# gasp_semg_bandpass_2nd_order.net
KiCad netlist of a schematic drawn in Altium Designer
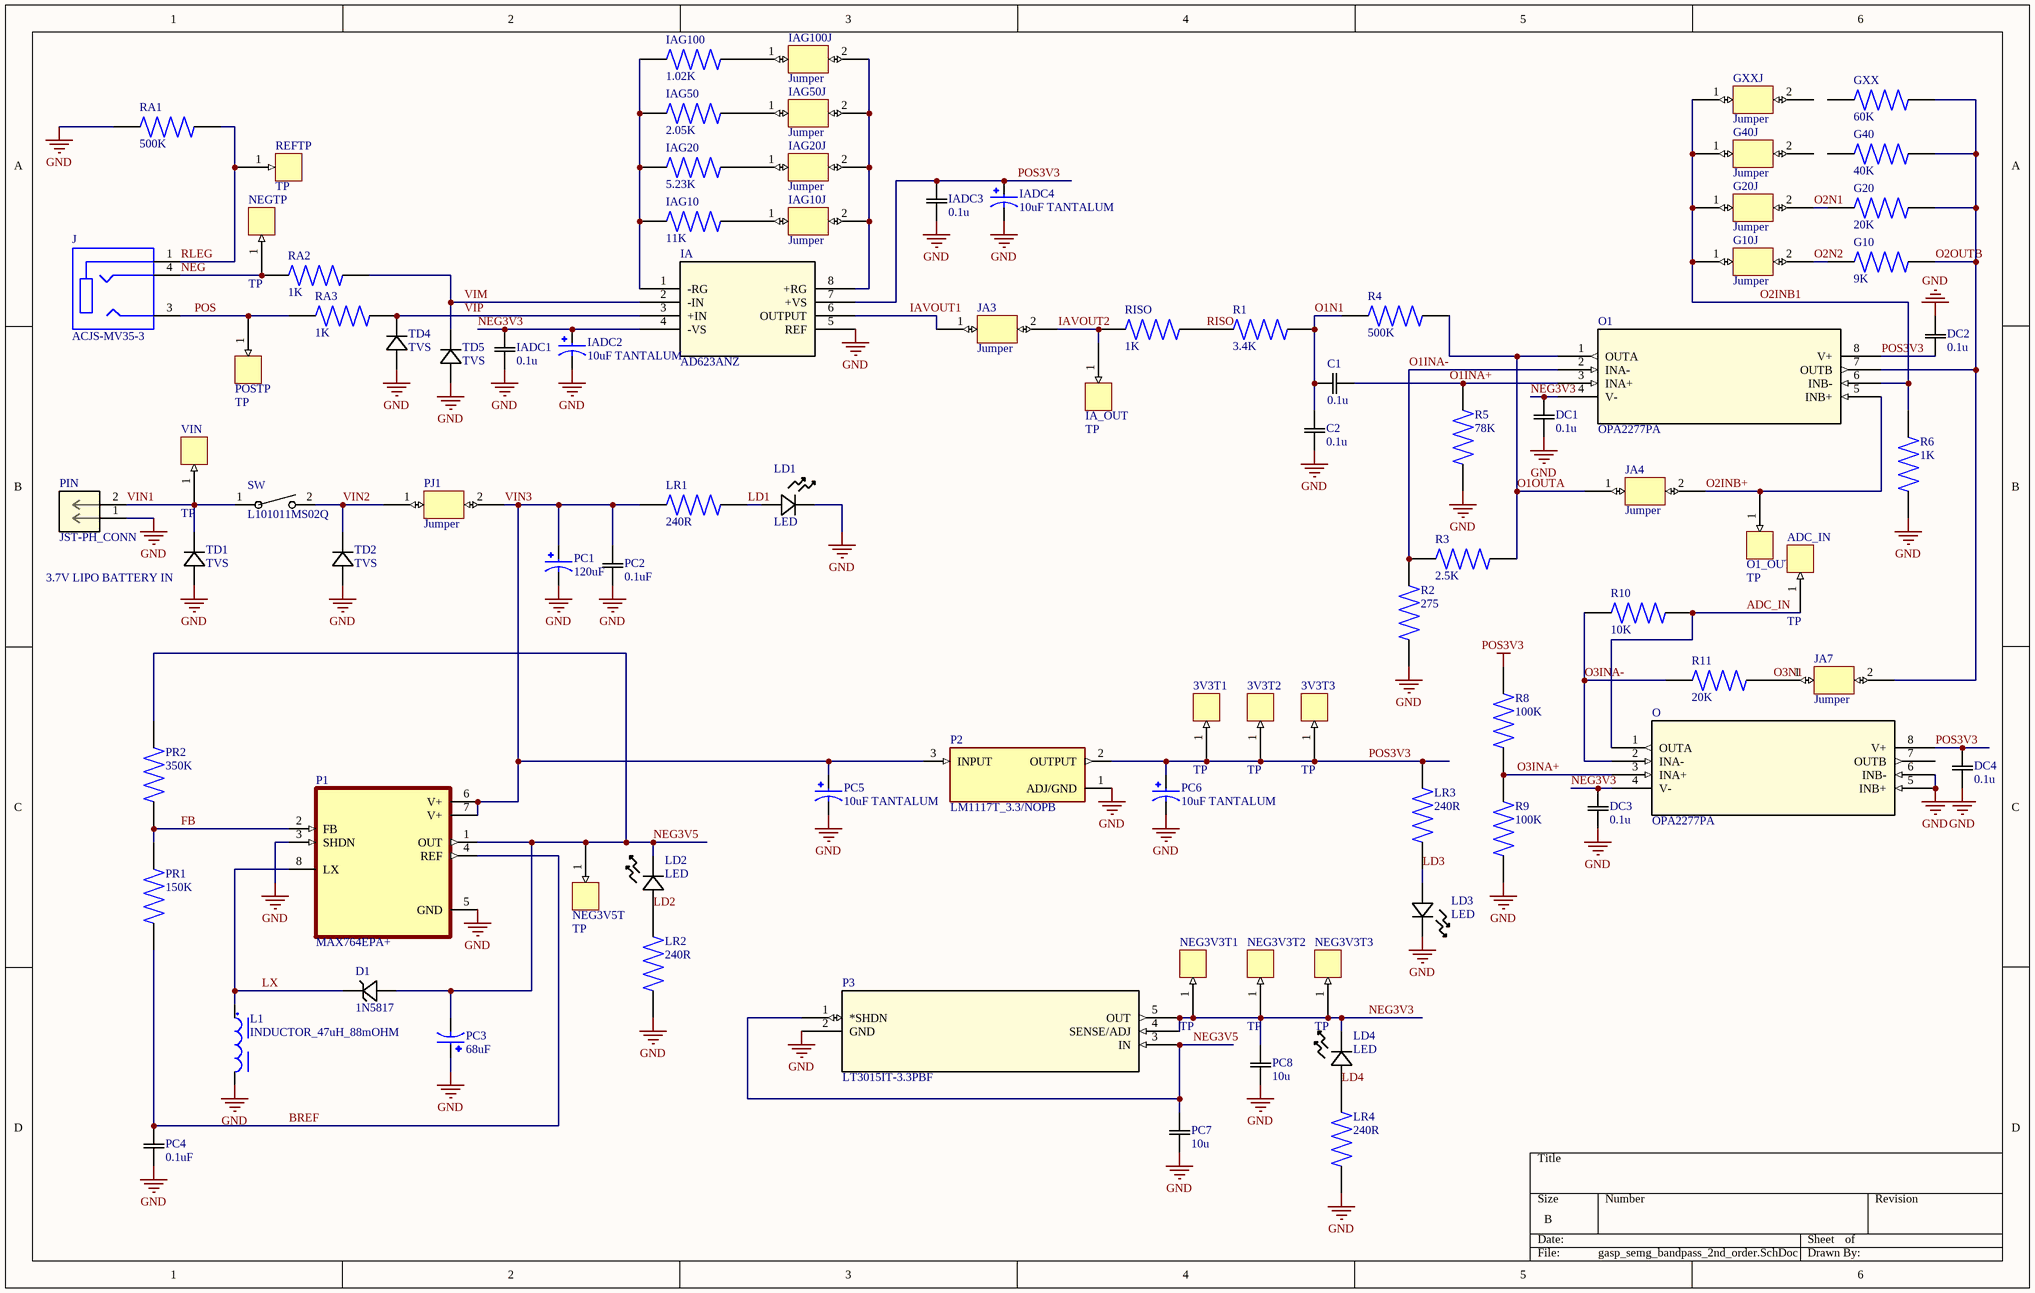
[diagram p0: gasp_semg_bandpass_2nd_order.SchDoc]

(export (version "E")
  (design (tool "Eeschema 10.0.6"))
  (components
    (comp (ref "3V3T1") (value "TP") (footprint "Test Point2") (libsource (lib "") (part "TP_1")))
    (comp (ref "3V3T2") (value "TP") (footprint "Test Point2") (libsource (lib "") (part "TP_1")))
    (comp (ref "3V3T3") (value "TP") (footprint "Test Point2") (libsource (lib "") (part "TP_1")))
    (comp (ref "ADC_IN") (value "TP") (footprint "Test Point2") (libsource (lib "") (part "TP_1")))
    (comp (ref "C1")
      (value "0.1u")
      (footprint "Axial")
      (description "Capacitor axial through-hole.")
      (fields
        (field (name "MANUFACTURER_PART_NUMBER") "C410C821J3G5TA")
        (field (name "COPYRIGHT") "Copyright (C) 2025 Ultra Librarian. All rights reserved.")
      )
      (libsource (lib "CAPACITOR_AXIAL_THROUGH_HOLE") (part "Cap"))
    )
    (comp (ref "C2")
      (value "0.1u")
      (footprint "Axial")
      (description "Capacitor axial through-hole.")
      (fields
        (field (name "MANUFACTURER_PART_NUMBER") "C410C821J3G5TA")
        (field (name "COPYRIGHT") "Copyright (C) 2025 Ultra Librarian. All rights reserved.")
      )
      (libsource (lib "CAPACITOR_AXIAL_THROUGH_HOLE") (part "Cap"))
    )
    (comp (ref "D1")
      (value "1N5817")
      (footprint "DO-41_STM")
      (description "20 V, 1 A axial Power Schottky Rectifier")
      (fields (field (name "COPYRIGHT") "Copyright (C) 2025 Ultra Librarian. All rights reserved."))
      (libsource (lib "DIODE_SCHOTTKY_1N5817") (part "1N5817"))
    )
    (comp (ref "DC1")
      (value "0.1u")
      (footprint "Axial")
      (description "Capacitor axial through-hole.")
      (fields
        (field (name "MANUFACTURER_PART_NUMBER") "C410C821J3G5TA")
        (field (name "COPYRIGHT") "Copyright (C) 2025 Ultra Librarian. All rights reserved.")
      )
      (libsource (lib "CAPACITOR_AXIAL_THROUGH_HOLE") (part "Cap"))
    )
    (comp (ref "DC2")
      (value "0.1u")
      (footprint "Axial")
      (description "Capacitor axial through-hole.")
      (fields
        (field (name "MANUFACTURER_PART_NUMBER") "C410C821J3G5TA")
        (field (name "COPYRIGHT") "Copyright (C) 2025 Ultra Librarian. All rights reserved.")
      )
      (libsource (lib "CAPACITOR_AXIAL_THROUGH_HOLE") (part "Cap"))
    )
    (comp (ref "DC3")
      (value "0.1u")
      (footprint "Axial")
      (description "Capacitor axial through-hole.")
      (fields
        (field (name "MANUFACTURER_PART_NUMBER") "C410C821J3G5TA")
        (field (name "COPYRIGHT") "Copyright (C) 2025 Ultra Librarian. All rights reserved.")
      )
      (libsource (lib "CAPACITOR_AXIAL_THROUGH_HOLE") (part "Cap"))
    )
    (comp (ref "DC4")
      (value "0.1u")
      (footprint "Axial")
      (description "Capacitor axial through-hole.")
      (fields
        (field (name "MANUFACTURER_PART_NUMBER") "C410C821J3G5TA")
        (field (name "COPYRIGHT") "Copyright (C) 2025 Ultra Librarian. All rights reserved.")
      )
      (libsource (lib "CAPACITOR_AXIAL_THROUGH_HOLE") (part "Cap"))
    )
    (comp (ref "G10")
      (value "9K")
      (footprint "Axial")
      (description "Through-hole resistor axial.")
      (fields (field (name "MF") "Yageo") (field (name "MP") "MFR-25FBF52-10K"))
      (libsource (lib "RESISTOR_THROUGH_HOLE") (part "Resistor"))
    )
    (comp (ref "G10J")
      (value "Jumper")
      (footprint "2-Pin Jumper")
      (description "0.1\" 2 pin jumper")
      (libsource (lib "JUMPER") (part "Jumper"))
    )
    (comp (ref "G20")
      (value "20K")
      (footprint "Axial")
      (description "Through-hole resistor axial.")
      (fields (field (name "MF") "Yageo") (field (name "MP") "MFR-25FBF52-10K"))
      (libsource (lib "RESISTOR_THROUGH_HOLE") (part "Resistor"))
    )
    (comp (ref "G20J")
      (value "Jumper")
      (footprint "2-Pin Jumper")
      (description "0.1\" 2 pin jumper")
      (libsource (lib "JUMPER") (part "Jumper"))
    )
    (comp (ref "G40")
      (value "40K")
      (footprint "Axial")
      (description "Through-hole resistor axial.")
      (fields (field (name "MF") "Yageo") (field (name "MP") "MFR-25FBF52-10K"))
      (libsource (lib "RESISTOR_THROUGH_HOLE") (part "Resistor"))
    )
    (comp (ref "G40J")
      (value "Jumper")
      (footprint "2-Pin Jumper")
      (description "0.1\" 2 pin jumper")
      (libsource (lib "JUMPER") (part "Jumper"))
    )
    (comp (ref "GXX")
      (value "60K")
      (footprint "Axial")
      (description "Through-hole resistor axial.")
      (fields (field (name "MF") "Yageo") (field (name "MP") "MFR-25FBF52-10K"))
      (libsource (lib "RESISTOR_THROUGH_HOLE") (part "Resistor"))
    )
    (comp (ref "GXXJ")
      (value "Jumper")
      (footprint "2-Pin Jumper")
      (description "0.1\" 2 pin jumper")
      (libsource (lib "JUMPER") (part "Jumper"))
    )
    (comp (ref "IA")
      (value "AD623ANZ")
      (footprint "8-PDIP")
      (description "Single and Dual-Supply, Rail-to-Rail, Low Cost Instrumentation Amplifier. AD623ANZ.")
      (fields (field (name "COPYRIGHT") "Copyright (C) 2025 Ultra Librarian. All rights reserved."))
      (libsource (lib "INSTRUMENTATION_AMP_DUAL_SINGLE_SUPPLY_AD623ANZ") (part "AD623ANZ"))
    )
    (comp (ref "IADC1")
      (value "0.1u")
      (footprint "Axial")
      (description "Capacitor axial through-hole.")
      (fields
        (field (name "MANUFACTURER_PART_NUMBER") "C410C821J3G5TA")
        (field (name "COPYRIGHT") "Copyright (C) 2025 Ultra Librarian. All rights reserved.")
      )
      (libsource (lib "CAPACITOR_AXIAL_THROUGH_HOLE") (part "Cap"))
    )
    (comp (ref "IADC2")
      (value "10uF TANTALUM")
      (footprint "CAP RADIAL")
      (description "CAPACITOR RADIAL.")
      (fields (field (name "MF") "Panasonic") (field (name "MP") "ECA1HM101"))
      (libsource (lib "") (part "CAP_1"))
    )
    (comp (ref "IADC3")
      (value "0.1u")
      (footprint "Axial")
      (description "Capacitor axial through-hole.")
      (fields
        (field (name "MANUFACTURER_PART_NUMBER") "C410C821J3G5TA")
        (field (name "COPYRIGHT") "Copyright (C) 2025 Ultra Librarian. All rights reserved.")
      )
      (libsource (lib "CAPACITOR_AXIAL_THROUGH_HOLE") (part "Cap"))
    )
    (comp (ref "IADC4")
      (value "10uF TANTALUM")
      (footprint "CAP RADIAL")
      (description "CAPACITOR RADIAL.")
      (fields (field (name "MF") "Panasonic") (field (name "MP") "ECA1HM101"))
      (libsource (lib "") (part "CAP_1"))
    )
    (comp (ref "IAG10")
      (value "11K")
      (footprint "Axial")
      (description "Through-hole resistor axial.")
      (fields (field (name "MF") "Yageo") (field (name "MP") "MFR-25FBF52-10K"))
      (libsource (lib "RESISTOR_THROUGH_HOLE") (part "Resistor"))
    )
    (comp (ref "IAG10J")
      (value "Jumper")
      (footprint "2-Pin Jumper")
      (description "0.1\" 2 pin jumper")
      (libsource (lib "JUMPER") (part "Jumper"))
    )
    (comp (ref "IAG20")
      (value "5.23K")
      (footprint "Axial")
      (description "Through-hole resistor axial.")
      (fields (field (name "MF") "Yageo") (field (name "MP") "MFR-25FBF52-10K"))
      (libsource (lib "RESISTOR_THROUGH_HOLE") (part "Resistor"))
    )
    (comp (ref "IAG20J")
      (value "Jumper")
      (footprint "2-Pin Jumper")
      (description "0.1\" 2 pin jumper")
      (libsource (lib "JUMPER") (part "Jumper"))
    )
    (comp (ref "IAG50")
      (value "2.05K")
      (footprint "Axial")
      (description "Through-hole resistor axial.")
      (fields (field (name "MF") "Yageo") (field (name "MP") "MFR-25FBF52-10K"))
      (libsource (lib "RESISTOR_THROUGH_HOLE") (part "Resistor"))
    )
    (comp (ref "IAG50J")
      (value "Jumper")
      (footprint "2-Pin Jumper")
      (description "0.1\" 2 pin jumper")
      (libsource (lib "JUMPER") (part "Jumper"))
    )
    (comp (ref "IAG100")
      (value "1.02K")
      (footprint "Axial")
      (description "Through-hole resistor axial.")
      (fields (field (name "MF") "Yageo") (field (name "MP") "MFR-25FBF52-10K"))
      (libsource (lib "RESISTOR_THROUGH_HOLE") (part "Resistor"))
    )
    (comp (ref "IAG100J")
      (value "Jumper")
      (footprint "2-Pin Jumper")
      (description "0.1\" 2 pin jumper")
      (libsource (lib "JUMPER") (part "Jumper"))
    )
    (comp (ref "IA_OUT") (value "TP") (footprint "Test Point2") (libsource (lib "") (part "TP_2")))
    (comp (ref "J")
      (value "ACJS-MV35-3")
      (footprint "AUDIO JACK II")
      (fields (field (name "MP") "SJ1-3553NG"))
      (libsource (lib "Audio Jack") (part "ACJS-MV35-3"))
    )
    (comp (ref "JA3")
      (value "Jumper")
      (footprint "2-Pin Jumper")
      (description "0.1\" 2 pin jumper")
      (libsource (lib "JUMPER") (part "Jumper"))
    )
    (comp (ref "JA4")
      (value "Jumper")
      (footprint "2-Pin Jumper")
      (description "0.1\" 2 pin jumper")
      (libsource (lib "JUMPER") (part "Jumper"))
    )
    (comp (ref "JA7")
      (value "Jumper")
      (footprint "2-Pin Jumper")
      (description "0.1\" 2 pin jumper")
      (libsource (lib "JUMPER") (part "Jumper"))
    )
    (comp (ref "L1")
      (value "INDUCTOR_47uH_88mOHM")
      (footprint "INDUCTOR_47uH_88mOHM")
      (fields (field (name "MF") "{'manufacturer': u'Wurth Electronics'}") (field (name "MP") "7447471470"))
      (libsource (lib "INDUCTOR_47uH_88mOHM_7447471470") (part "INDUCTOR_47uH_88mOHM"))
    )
    (comp (ref "LD1")
      (value "LED")
      (footprint "LED_5MM_RADIAL")
      (description "LED_5MM_RADIAL")
      (fields
        (field (name "MANUFACTURER_PART_NUMBER") "C503B-BCN-CV0Z0461")
        (field (name "COPYRIGHT") "Copyright (C) 2025 Ultra Librarian. All rights reserved.")
      )
      (libsource (lib "LED_5MM_RADIAL") (part "LED"))
    )
    (comp (ref "LD2")
      (value "LED")
      (footprint "LED_5MM_RADIAL")
      (description "LED_5MM_RADIAL")
      (fields
        (field (name "MANUFACTURER_PART_NUMBER") "C503B-BCN-CV0Z0461")
        (field (name "COPYRIGHT") "Copyright (C) 2025 Ultra Librarian. All rights reserved.")
      )
      (libsource (lib "LED_5MM_RADIAL") (part "LED"))
    )
    (comp (ref "LD3")
      (value "LED")
      (footprint "LED_5MM_RADIAL")
      (description "LED_5MM_RADIAL")
      (fields
        (field (name "MANUFACTURER_PART_NUMBER") "C503B-BCN-CV0Z0461")
        (field (name "COPYRIGHT") "Copyright (C) 2025 Ultra Librarian. All rights reserved.")
      )
      (libsource (lib "LED_5MM_RADIAL") (part "LED"))
    )
    (comp (ref "LD4")
      (value "LED")
      (footprint "LED_5MM_RADIAL")
      (description "LED_5MM_RADIAL")
      (fields
        (field (name "MANUFACTURER_PART_NUMBER") "C503B-BCN-CV0Z0461")
        (field (name "COPYRIGHT") "Copyright (C) 2025 Ultra Librarian. All rights reserved.")
      )
      (libsource (lib "LED_5MM_RADIAL") (part "LED"))
    )
    (comp (ref "LR1")
      (value "240R")
      (footprint "Axial")
      (description "Through-hole resistor axial.")
      (fields (field (name "MF") "Yageo") (field (name "MP") "MFR-25FBF52-10K"))
      (libsource (lib "RESISTOR_THROUGH_HOLE") (part "Resistor"))
    )
    (comp (ref "LR2")
      (value "240R")
      (footprint "Axial")
      (description "Through-hole resistor axial.")
      (fields (field (name "MF") "Yageo") (field (name "MP") "MFR-25FBF52-10K"))
      (libsource (lib "RESISTOR_THROUGH_HOLE") (part "Resistor"))
    )
    (comp (ref "LR3")
      (value "240R")
      (footprint "Axial")
      (description "Through-hole resistor axial.")
      (fields (field (name "MF") "Yageo") (field (name "MP") "MFR-25FBF52-10K"))
      (libsource (lib "RESISTOR_THROUGH_HOLE") (part "Resistor"))
    )
    (comp (ref "LR4")
      (value "240R")
      (footprint "Axial")
      (description "Through-hole resistor axial.")
      (fields (field (name "MF") "Yageo") (field (name "MP") "MFR-25FBF52-10K"))
      (libsource (lib "RESISTOR_THROUGH_HOLE") (part "Resistor"))
    )
    (comp (ref "NEG3V3T1") (value "TP") (footprint "Test Point2") (libsource (lib "") (part "TP_1")))
    (comp (ref "NEG3V3T2") (value "TP") (footprint "Test Point2") (libsource (lib "") (part "TP_1")))
    (comp (ref "NEG3V3T3") (value "TP") (footprint "Test Point2") (libsource (lib "") (part "TP_1")))
    (comp (ref "NEG3V5T") (value "TP") (footprint "Test Point2") (libsource (lib "") (part "TP_2")))
    (comp (ref "NEGTP") (value "TP") (footprint "Test Point2") (libsource (lib "") (part "TP_1")))
    (comp (ref "O")
      (value "OPA2277PA")
      (footprint "8-PDIP")
      (description "10ÂµV, 0.1ÂµV/ËšC, High-Precision, Low-Power Operational Amplifier 8-PDIP")
      (fields (field (name "COPYRIGHT") "Copyright (C) 2025 Ultra Librarian. All rights reserved."))
      (libsource (lib "OPAMP_DUAL_SUPPLY_8-PDIP_OPA2277PA") (part "OPA2277PA"))
    )
    (comp (ref "O1")
      (value "OPA2277PA")
      (footprint "8-PDIP")
      (description "10ÂµV, 0.1ÂµV/ËšC, High-Precision, Low-Power Operational Amplifier 8-PDIP")
      (fields (field (name "COPYRIGHT") "Copyright (C) 2025 Ultra Librarian. All rights reserved."))
      (libsource (lib "OPAMP_DUAL_SUPPLY_8-PDIP_OPA2277PA") (part "OPA2277PA"))
    )
    (comp (ref "O1_OUT") (value "TP") (footprint "Test Point2") (libsource (lib "") (part "TP_2")))
    (comp (ref "P1")
      (value "MAX764EPA+")
      (footprint "8-PDIP")
      (description "IC REG BCK BST ADJ/-5V 8DIP")
      (fields (field (name "MF") "Maxim Integrated"))
      (libsource (lib "BUCK_BOOST_-1V_TO_-16V_OUTPUT_MAX764EPA") (part "MAX764EPA+"))
    )
    (comp (ref "P2")
      (value "LM1117T_3.3/NOPB")
      (footprint "TO-220-3")
      (description "3.3V Linear Voltage Regulator IC Positive Fixed 1 Output 800mA TO-220-3.")
      (fields (field (name "MF") "Texas Instruments") (field (name "MP") "LM1117T-3.3/NOPB"))
      (libsource (lib "LDO_3V3_TO-220-3_LM1117T-3V3_NOPB") (part "LM1117T_3.3/NOPB"))
    )
    (comp (ref "P3")
      (value "LT3015IT-3.3PBF")
      (footprint "TO220-5_T_LIT")
      (description "Linear Voltage Regulator IC Negative Fixed 1 Output 1.5A TO-220-5No Description Available")
      (fields
        (field (name "MANUFACTURER_PART_NUMBER") "LT3015IT-3.3#PBF")
        (field (name "COPYRIGHT") "Copyright (C) 2025 Ultra Librarian. All rights reserved.")
      )
      (libsource (lib "LDO_NEGATIVE_3V3_LT3015IT-3P3PBF") (part "LT3015IT-3.3PBF"))
    )
    (comp (ref "PC1")
      (value "120uF")
      (footprint "CAP RADIAL")
      (description "CAPACITOR RADIAL.")
      (fields (field (name "MF") "Panasonic") (field (name "MP") "ECA1HM101"))
      (libsource (lib "") (part "CAP_1"))
    )
    (comp (ref "PC2")
      (value "0.1uF")
      (footprint "Axial")
      (description "Capacitor axial through-hole.")
      (fields
        (field (name "MANUFACTURER_PART_NUMBER") "C410C821J3G5TA")
        (field (name "COPYRIGHT") "Copyright (C) 2025 Ultra Librarian. All rights reserved.")
      )
      (libsource (lib "CAPACITOR_AXIAL_THROUGH_HOLE") (part "Cap"))
    )
    (comp (ref "PC3")
      (value "68uF")
      (footprint "CAP RADIAL")
      (description "CAPACITOR RADIAL.")
      (fields (field (name "MF") "Panasonic") (field (name "MP") "ECA1HM101"))
      (libsource (lib "CAPACITOR_ELEC_RADIAL") (part "CAP"))
    )
    (comp (ref "PC4")
      (value "0.1uF")
      (footprint "Axial")
      (description "Capacitor axial through-hole.")
      (fields
        (field (name "MANUFACTURER_PART_NUMBER") "C410C821J3G5TA")
        (field (name "COPYRIGHT") "Copyright (C) 2025 Ultra Librarian. All rights reserved.")
      )
      (libsource (lib "CAPACITOR_AXIAL_THROUGH_HOLE") (part "Cap"))
    )
    (comp (ref "PC5")
      (value "10uF TANTALUM")
      (footprint "CAP RADIAL")
      (description "CAPACITOR RADIAL.")
      (fields (field (name "MF") "Panasonic") (field (name "MP") "ECA1HM101"))
      (libsource (lib "") (part "CAP_1"))
    )
    (comp (ref "PC6")
      (value "10uF TANTALUM")
      (footprint "CAP RADIAL")
      (description "CAPACITOR RADIAL.")
      (fields (field (name "MF") "Panasonic") (field (name "MP") "ECA1HM101"))
      (libsource (lib "") (part "CAP_1"))
    )
    (comp (ref "PC7")
      (value "10u")
      (footprint "Axial")
      (description "Capacitor axial through-hole.")
      (fields
        (field (name "MANUFACTURER_PART_NUMBER") "C410C821J3G5TA")
        (field (name "COPYRIGHT") "Copyright (C) 2025 Ultra Librarian. All rights reserved.")
      )
      (libsource (lib "CAPACITOR_AXIAL_THROUGH_HOLE") (part "Cap"))
    )
    (comp (ref "PC8")
      (value "10u")
      (footprint "Axial")
      (description "Capacitor axial through-hole.")
      (fields
        (field (name "MANUFACTURER_PART_NUMBER") "C410C821J3G5TA")
        (field (name "COPYRIGHT") "Copyright (C) 2025 Ultra Librarian. All rights reserved.")
      )
      (libsource (lib "CAPACITOR_AXIAL_THROUGH_HOLE") (part "Cap"))
    )
    (comp (ref "PIN")
      (value "JST-PH_CONN")
      (footprint "CONN2_B2B-PH-K-S_JST")
      (description "CONN HEADER VERT 2POS 2MM")
      (libsource (lib "JST-PH_CONN_HEADER_VERT_2POS_2MM") (part "JST-PH_CONN"))
    )
    (comp (ref "PJ1")
      (value "Jumper")
      (footprint "2-Pin Jumper")
      (description "0.1\" 2 pin jumper")
      (libsource (lib "JUMPER") (part "Jumper"))
    )
    (comp (ref "POSTP") (value "TP") (footprint "Test Point2") (libsource (lib "") (part "TP_2")))
    (comp (ref "PR1")
      (value "150K")
      (footprint "Axial")
      (description "Through-hole resistor axial.")
      (fields (field (name "MF") "Yageo") (field (name "MP") "MFR-25FBF52-10K"))
      (libsource (lib "RESISTOR_THROUGH_HOLE") (part "Resistor"))
    )
    (comp (ref "PR2")
      (value "350K")
      (footprint "Axial")
      (description "Through-hole resistor axial.")
      (fields (field (name "MF") "Yageo") (field (name "MP") "MFR-25FBF52-10K"))
      (libsource (lib "RESISTOR_THROUGH_HOLE") (part "Resistor"))
    )
    (comp (ref "R1")
      (value "3.4K")
      (footprint "Axial")
      (description "Through-hole resistor axial.")
      (fields (field (name "MF") "Yageo") (field (name "MP") "MFR-25FBF52-10K"))
      (libsource (lib "RESISTOR_THROUGH_HOLE") (part "Resistor"))
    )
    (comp (ref "R2")
      (value "275")
      (footprint "Axial")
      (description "Through-hole resistor axial.")
      (fields (field (name "MF") "Yageo") (field (name "MP") "MFR-25FBF52-10K"))
      (libsource (lib "RESISTOR_THROUGH_HOLE") (part "Resistor"))
    )
    (comp (ref "R3")
      (value "2.5K")
      (footprint "Axial")
      (description "Through-hole resistor axial.")
      (fields (field (name "MF") "Yageo") (field (name "MP") "MFR-25FBF52-10K"))
      (libsource (lib "RESISTOR_THROUGH_HOLE") (part "Resistor"))
    )
    (comp (ref "R4")
      (value "500K")
      (footprint "Axial")
      (description "Through-hole resistor axial.")
      (fields (field (name "MF") "Yageo") (field (name "MP") "MFR-25FBF52-10K"))
      (libsource (lib "RESISTOR_THROUGH_HOLE") (part "Resistor"))
    )
    (comp (ref "R5")
      (value "78K")
      (footprint "Axial")
      (description "Through-hole resistor axial.")
      (fields (field (name "MF") "Yageo") (field (name "MP") "MFR-25FBF52-10K"))
      (libsource (lib "RESISTOR_THROUGH_HOLE") (part "Resistor"))
    )
    (comp (ref "R6")
      (value "1K")
      (footprint "Axial")
      (description "Through-hole resistor axial.")
      (fields (field (name "MF") "Yageo") (field (name "MP") "MFR-25FBF52-10K"))
      (libsource (lib "RESISTOR_THROUGH_HOLE") (part "Resistor"))
    )
    (comp (ref "R8")
      (value "100K")
      (footprint "Axial")
      (description "Through-hole resistor axial.")
      (fields (field (name "MF") "Yageo") (field (name "MP") "MFR-25FBF52-10K"))
      (libsource (lib "RESISTOR_THROUGH_HOLE") (part "Resistor"))
    )
    (comp (ref "R9")
      (value "100K")
      (footprint "Axial")
      (description "Through-hole resistor axial.")
      (fields (field (name "MF") "Yageo") (field (name "MP") "MFR-25FBF52-10K"))
      (libsource (lib "RESISTOR_THROUGH_HOLE") (part "Resistor"))
    )
    (comp (ref "R10")
      (value "10K")
      (footprint "Axial")
      (description "Through-hole resistor axial.")
      (fields (field (name "MF") "Yageo") (field (name "MP") "MFR-25FBF52-10K"))
      (libsource (lib "RESISTOR_THROUGH_HOLE") (part "Resistor"))
    )
    (comp (ref "R11")
      (value "20K")
      (footprint "Axial")
      (description "Through-hole resistor axial.")
      (fields (field (name "MF") "Yageo") (field (name "MP") "MFR-25FBF52-10K"))
      (libsource (lib "RESISTOR_THROUGH_HOLE") (part "Resistor"))
    )
    (comp (ref "RA1")
      (value "500K")
      (footprint "Axial")
      (description "Through-hole resistor axial.")
      (fields (field (name "MF") "Yageo") (field (name "MP") "MFR-25FBF52-10K"))
      (libsource (lib "RESISTOR_THROUGH_HOLE") (part "Resistor"))
    )
    (comp (ref "RA2")
      (value "1K")
      (footprint "Axial")
      (description "Through-hole resistor axial.")
      (fields (field (name "MF") "Yageo") (field (name "MP") "MFR-25FBF52-10K"))
      (libsource (lib "RESISTOR_THROUGH_HOLE") (part "Resistor"))
    )
    (comp (ref "RA3")
      (value "1K")
      (footprint "Axial")
      (description "Through-hole resistor axial.")
      (fields (field (name "MF") "Yageo") (field (name "MP") "MFR-25FBF52-10K"))
      (libsource (lib "RESISTOR_THROUGH_HOLE") (part "Resistor"))
    )
    (comp (ref "REFTP") (value "TP") (footprint "Test Point2") (libsource (lib "Test Point") (part "TP")))
    (comp (ref "RISO")
      (value "1K")
      (footprint "Axial")
      (description "Through-hole resistor axial.")
      (fields (field (name "MF") "Yageo") (field (name "MP") "MFR-25FBF52-10K"))
      (libsource (lib "RESISTOR_THROUGH_HOLE") (part "Resistor"))
    )
    (comp (ref "SW")
      (value "L101011MS02Q")
      (footprint "SW_1MS02Q_CNK")
      (description "Slide Switch SPST Through Hole.")
      (libsource (lib "SWITCH_SLIDE__SPST_L101011MS02Q") (part "L101011MS02Q"))
    )
    (comp (ref "TD1")
      (value "TVS")
      (footprint "TVS_DIODE_5VWM")
      (description "9.2V Clamp 55.4A Ipp Tvs Diode Through Hole DO-204AC (DO-15).")
      (fields
        (field (name "MANUFACTURER_PART_NUMBER") "SA5.0CA")
        (field (name "COPYRIGHT") "Copyright (C) 2025 Ultra Librarian. All rights reserved.")
      )
      (libsource (lib "TVS_DIODE_5VWM") (part "TVS"))
    )
    (comp (ref "TD2")
      (value "TVS")
      (footprint "TVS_DIODE_5VWM")
      (description "9.2V Clamp 55.4A Ipp Tvs Diode Through Hole DO-204AC (DO-15).")
      (fields
        (field (name "MANUFACTURER_PART_NUMBER") "SA5.0CA")
        (field (name "COPYRIGHT") "Copyright (C) 2025 Ultra Librarian. All rights reserved.")
      )
      (libsource (lib "TVS_DIODE_5VWM") (part "TVS"))
    )
    (comp (ref "TD4")
      (value "TVS")
      (footprint "TVS_DIODE_5VWM")
      (description "9.2V Clamp 55.4A Ipp Tvs Diode Through Hole DO-204AC (DO-15).")
      (fields
        (field (name "MANUFACTURER_PART_NUMBER") "SA5.0CA")
        (field (name "COPYRIGHT") "Copyright (C) 2025 Ultra Librarian. All rights reserved.")
      )
      (libsource (lib "TVS_DIODE_5VWM") (part "TVS"))
    )
    (comp (ref "TD5")
      (value "TVS")
      (footprint "TVS_DIODE_5VWM")
      (description "9.2V Clamp 55.4A Ipp Tvs Diode Through Hole DO-204AC (DO-15).")
      (fields
        (field (name "MANUFACTURER_PART_NUMBER") "SA5.0CA")
        (field (name "COPYRIGHT") "Copyright (C) 2025 Ultra Librarian. All rights reserved.")
      )
      (libsource (lib "TVS_DIODE_5VWM") (part "TVS"))
    )
    (comp (ref "VIN") (value "TP") (footprint "Test Point2") (libsource (lib "") (part "TP_1")))
  )
  (nets
    (net (code "1") (name "/ADC_IN") (class "Default")
      (node (ref "ADC_IN") (pin "1") (pintype "input"))
      (node (ref "O") (pin "1") (pinfunction "OUTA_1") (pintype "output"))
      (node (ref "R10") (pin "2") (pinfunction "2_2") (pintype "passive"))
    )
    (net (code "2") (name "/BREF") (class "Default")
      (node (ref "P1") (pin "4") (pinfunction "REF_4") (pintype "output"))
      (node (ref "PC4") (pin "1") (pinfunction "1_1") (pintype "passive"))
      (node (ref "PR1") (pin "1") (pinfunction "1_1") (pintype "passive"))
    )
    (net (code "3") (name "/FB") (class "Default")
      (node (ref "P1") (pin "2") (pinfunction "FB_2") (pintype "input"))
      (node (ref "PR1") (pin "2") (pinfunction "2_2") (pintype "passive"))
      (node (ref "PR2") (pin "1") (pinfunction "1_1") (pintype "passive"))
    )
    (net (code "4") (name "/IAVOUT1") (class "Default")
      (node (ref "IA") (pin "6") (pinfunction "OUTPUT_6") (pintype "passive"))
      (node (ref "JA3") (pin "1") (pintype "bidirectional"))
    )
    (net (code "5") (name "/IAVOUT2") (class "Default")
      (node (ref "IA_OUT") (pin "1") (pintype "input"))
      (node (ref "JA3") (pin "2") (pintype "bidirectional"))
      (node (ref "RISO") (pin "1") (pinfunction "1_1") (pintype "passive"))
    )
    (net (code "6") (name "/LD1") (class "Default")
      (node (ref "LD1") (pin "2") (pinfunction "2_2") (pintype "passive"))
      (node (ref "LR1") (pin "1") (pinfunction "1_1") (pintype "passive"))
    )
    (net (code "7") (name "/LD2") (class "Default")
      (node (ref "LD2") (pin "2") (pinfunction "2_2") (pintype "passive"))
      (node (ref "LR2") (pin "2") (pinfunction "2_2") (pintype "passive"))
    )
    (net (code "8") (name "/LD3") (class "Default")
      (node (ref "LD3") (pin "2") (pinfunction "2_2") (pintype "passive"))
      (node (ref "LR3") (pin "1") (pinfunction "1_1") (pintype "passive"))
    )
    (net (code "9") (name "/LD4") (class "Default")
      (node (ref "LD4") (pin "2") (pinfunction "2_2") (pintype "passive"))
      (node (ref "LR4") (pin "2") (pinfunction "2_2") (pintype "passive"))
    )
    (net (code "10") (name "/LX") (class "Default")
      (node (ref "D1") (pin "1") (pinfunction "1_1") (pintype "passive"))
      (node (ref "L1") (pin "1") (pinfunction "1_1") (pintype "passive"))
      (node (ref "P1") (pin "8") (pinfunction "LX_8") (pintype "passive"))
    )
    (net (code "11") (name "/NEG") (class "Default")
      (node (ref "J") (pin "4") (pinfunction "4_4") (pintype "passive"))
      (node (ref "NEGTP") (pin "1") (pintype "input"))
      (node (ref "RA2") (pin "2") (pinfunction "2_2") (pintype "passive"))
    )
    (net (code "12") (name "/NEG3V3") (class "Default")
      (node (ref "DC1") (pin "1") (pinfunction "1_1") (pintype "passive"))
      (node (ref "DC3") (pin "1") (pinfunction "1_1") (pintype "passive"))
      (node (ref "IA") (pin "4") (pinfunction "-VS_4") (pintype "power_in"))
      (node (ref "IADC1") (pin "1") (pinfunction "1_1") (pintype "passive"))
      (node (ref "IADC2") (pin "P") (pinfunction "P_P") (pintype "passive"))
      (node (ref "LD4") (pin "1") (pinfunction "1_1") (pintype "passive"))
      (node (ref "NEG3V3T1") (pin "1") (pintype "input"))
      (node (ref "NEG3V3T2") (pin "1") (pintype "input"))
      (node (ref "NEG3V3T3") (pin "1") (pintype "input"))
      (node (ref "O") (pin "4") (pinfunction "V-_4") (pintype "power_in"))
      (node (ref "O1") (pin "4") (pinfunction "V-_4") (pintype "power_in"))
      (node (ref "P3") (pin "4") (pinfunction "SENSE/ADJ_4") (pintype "input"))
      (node (ref "P3") (pin "5") (pinfunction "OUT_5") (pintype "output"))
      (node (ref "PC8") (pin "1") (pinfunction "1_1") (pintype "passive"))
    )
    (net (code "13") (name "/NEG3V5") (class "Default")
      (node (ref "D1") (pin "2") (pinfunction "2_2") (pintype "passive"))
      (node (ref "LD2") (pin "1") (pinfunction "1_1") (pintype "passive"))
      (node (ref "NEG3V5T") (pin "1") (pintype "input"))
      (node (ref "P1") (pin "1") (pinfunction "OUT_1") (pintype "output"))
      (node (ref "P3") (pin "1") (pinfunction "*SHDN_1") (pintype "bidirectional"))
      (node (ref "P3") (pin "3") (pinfunction "IN_3") (pintype "input"))
      (node (ref "PC3") (pin "N") (pinfunction "N_N") (pintype "passive"))
      (node (ref "PC7") (pin "1") (pinfunction "1_1") (pintype "passive"))
      (node (ref "PR2") (pin "2") (pinfunction "2_2") (pintype "passive"))
    )
    (net (code "14") (name "/O1INA+") (class "Default")
      (node (ref "C1") (pin "2") (pinfunction "2_2") (pintype "passive"))
      (node (ref "O1") (pin "3") (pinfunction "INA+_3") (pintype "input"))
      (node (ref "R5") (pin "1") (pinfunction "1_1") (pintype "passive"))
    )
    (net (code "15") (name "/O1INA-") (class "Default")
      (node (ref "O1") (pin "2") (pinfunction "INA-_2") (pintype "input"))
      (node (ref "R2") (pin "1") (pinfunction "1_1") (pintype "passive"))
      (node (ref "R3") (pin "2") (pinfunction "2_2") (pintype "passive"))
    )
    (net (code "16") (name "/O1N1") (class "Default")
      (node (ref "C1") (pin "1") (pinfunction "1_1") (pintype "passive"))
      (node (ref "C2") (pin "1") (pinfunction "1_1") (pintype "passive"))
      (node (ref "R1") (pin "1") (pinfunction "1_1") (pintype "passive"))
      (node (ref "R4") (pin "1") (pinfunction "1_1") (pintype "passive"))
    )
    (net (code "17") (name "/O1OUTA") (class "Default")
      (node (ref "JA4") (pin "1") (pintype "bidirectional"))
      (node (ref "O1") (pin "1") (pinfunction "OUTA_1") (pintype "output"))
      (node (ref "R3") (pin "1") (pinfunction "1_1") (pintype "passive"))
      (node (ref "R4") (pin "2") (pinfunction "2_2") (pintype "passive"))
    )
    (net (code "18") (name "/O2INB+") (class "Default")
      (node (ref "JA4") (pin "2") (pintype "bidirectional"))
      (node (ref "O1") (pin "5") (pinfunction "INB+_5") (pintype "input"))
      (node (ref "O1_OUT") (pin "1") (pintype "input"))
    )
    (net (code "19") (name "/O2INB1") (class "Default")
      (node (ref "G10J") (pin "1") (pintype "bidirectional"))
      (node (ref "G20J") (pin "1") (pintype "bidirectional"))
      (node (ref "G40J") (pin "1") (pintype "bidirectional"))
      (node (ref "GXXJ") (pin "1") (pintype "bidirectional"))
      (node (ref "O1") (pin "6") (pinfunction "INB-_6") (pintype "input"))
      (node (ref "R6") (pin "1") (pinfunction "1_1") (pintype "passive"))
    )
    (net (code "20") (name "/O2N1") (class "Default")
      (node (ref "G20") (pin "1") (pinfunction "1_1") (pintype "passive"))
      (node (ref "G20J") (pin "2") (pintype "bidirectional"))
    )
    (net (code "21") (name "/O2N2") (class "Default")
      (node (ref "G10") (pin "1") (pinfunction "1_1") (pintype "passive"))
      (node (ref "G10J") (pin "2") (pintype "bidirectional"))
    )
    (net (code "22") (name "/O2OUTB") (class "Default")
      (node (ref "G10") (pin "2") (pinfunction "2_2") (pintype "passive"))
      (node (ref "G20") (pin "2") (pinfunction "2_2") (pintype "passive"))
      (node (ref "G40") (pin "2") (pinfunction "2_2") (pintype "passive"))
      (node (ref "GXX") (pin "2") (pinfunction "2_2") (pintype "passive"))
      (node (ref "JA7") (pin "2") (pintype "bidirectional"))
      (node (ref "O1") (pin "7") (pinfunction "OUTB_7") (pintype "output"))
    )
    (net (code "23") (name "/O3INA+") (class "Default")
      (node (ref "O") (pin "3") (pinfunction "INA+_3") (pintype "input"))
      (node (ref "R8") (pin "2") (pinfunction "2_2") (pintype "passive"))
      (node (ref "R9") (pin "1") (pinfunction "1_1") (pintype "passive"))
    )
    (net (code "24") (name "/O3INA-") (class "Default")
      (node (ref "O") (pin "2") (pinfunction "INA-_2") (pintype "input"))
      (node (ref "R10") (pin "1") (pinfunction "1_1") (pintype "passive"))
      (node (ref "R11") (pin "1") (pinfunction "1_1") (pintype "passive"))
    )
    (net (code "25") (name "/O3N1") (class "Default")
      (node (ref "JA7") (pin "1") (pintype "bidirectional"))
      (node (ref "R11") (pin "2") (pinfunction "2_2") (pintype "passive"))
    )
    (net (code "26") (name "/POS") (class "Default")
      (node (ref "J") (pin "3") (pinfunction "3_3") (pintype "passive"))
      (node (ref "POSTP") (pin "1") (pintype "input"))
      (node (ref "RA3") (pin "2") (pinfunction "2_2") (pintype "passive"))
    )
    (net (code "27") (name "/RISO") (class "Default")
      (node (ref "R1") (pin "2") (pinfunction "2_2") (pintype "passive"))
      (node (ref "RISO") (pin "2") (pinfunction "2_2") (pintype "passive"))
    )
    (net (code "28") (name "/RLEG") (class "Default")
      (node (ref "J") (pin "1") (pinfunction "1_1") (pintype "passive"))
      (node (ref "RA1") (pin "1") (pinfunction "1_1") (pintype "passive"))
      (node (ref "REFTP") (pin "1") (pintype "input"))
    )
    (net (code "29") (name "/VIM") (class "Default")
      (node (ref "IA") (pin "2") (pinfunction "-IN_2") (pintype "passive"))
      (node (ref "RA2") (pin "1") (pinfunction "1_1") (pintype "passive"))
      (node (ref "TD5") (pin "1") (pinfunction "1_1") (pintype "passive"))
    )
    (net (code "30") (name "/VIN1") (class "Default")
      (node (ref "PIN") (pin "2") (pinfunction "2_2") (pintype "passive"))
      (node (ref "SW") (pin "1") (pinfunction "1_1") (pintype "passive"))
      (node (ref "TD1") (pin "1") (pinfunction "1_1") (pintype "passive"))
      (node (ref "VIN") (pin "1") (pintype "input"))
    )
    (net (code "31") (name "/VIN2") (class "Default")
      (node (ref "PJ1") (pin "1") (pintype "bidirectional"))
      (node (ref "SW") (pin "2") (pinfunction "2_2") (pintype "passive"))
      (node (ref "TD2") (pin "1") (pinfunction "1_1") (pintype "passive"))
    )
    (net (code "32") (name "/VIN3") (class "Default")
      (node (ref "LR1") (pin "2") (pinfunction "2_2") (pintype "passive"))
      (node (ref "P1") (pin "6") (pinfunction "V+_6") (pintype "power_in"))
      (node (ref "P1") (pin "7") (pinfunction "V+_7") (pintype "power_in"))
      (node (ref "P2") (pin "3") (pinfunction "INPUT_3") (pintype "input"))
      (node (ref "PC1") (pin "P") (pinfunction "P_P") (pintype "passive"))
      (node (ref "PC2") (pin "1") (pinfunction "1_1") (pintype "passive"))
      (node (ref "PC5") (pin "P") (pinfunction "P_P") (pintype "passive"))
      (node (ref "PJ1") (pin "2") (pintype "bidirectional"))
    )
    (net (code "33") (name "/VIP") (class "Default")
      (node (ref "IA") (pin "3") (pinfunction "+IN_3") (pintype "passive"))
      (node (ref "RA3") (pin "1") (pinfunction "1_1") (pintype "passive"))
      (node (ref "TD4") (pin "1") (pinfunction "1_1") (pintype "passive"))
    )
    (net (code "34") (name "GND") (class "Default")
      (node (ref "C2") (pin "2") (pinfunction "2_2") (pintype "passive"))
      (node (ref "DC1") (pin "2") (pinfunction "2_2") (pintype "passive"))
      (node (ref "DC2") (pin "2") (pinfunction "2_2") (pintype "passive"))
      (node (ref "DC3") (pin "2") (pinfunction "2_2") (pintype "passive"))
      (node (ref "DC4") (pin "2") (pinfunction "2_2") (pintype "passive"))
      (node (ref "IA") (pin "5") (pinfunction "REF_5") (pintype "passive"))
      (node (ref "IADC1") (pin "2") (pinfunction "2_2") (pintype "passive"))
      (node (ref "IADC2") (pin "N") (pinfunction "N_N") (pintype "passive"))
      (node (ref "IADC3") (pin "2") (pinfunction "2_2") (pintype "passive"))
      (node (ref "IADC4") (pin "N") (pinfunction "N_N") (pintype "passive"))
      (node (ref "L1") (pin "2") (pinfunction "2_2") (pintype "passive"))
      (node (ref "LD1") (pin "1") (pinfunction "1_1") (pintype "passive"))
      (node (ref "LD3") (pin "1") (pinfunction "1_1") (pintype "passive"))
      (node (ref "LR2") (pin "1") (pinfunction "1_1") (pintype "passive"))
      (node (ref "LR4") (pin "1") (pinfunction "1_1") (pintype "passive"))
      (node (ref "O") (pin "5") (pinfunction "INB+_5") (pintype "input"))
      (node (ref "O") (pin "6") (pinfunction "INB-_6") (pintype "input"))
      (node (ref "P1") (pin "3") (pinfunction "SHDN_3") (pintype "input"))
      (node (ref "P1") (pin "5") (pinfunction "GND_5") (pintype "power_in"))
      (node (ref "P2") (pin "1") (pinfunction "ADJ/GND_1") (pintype "power_in"))
      (node (ref "P3") (pin "2") (pinfunction "GND_2") (pintype "power_in"))
      (node (ref "PC1") (pin "N") (pinfunction "N_N") (pintype "passive"))
      (node (ref "PC2") (pin "2") (pinfunction "2_2") (pintype "passive"))
      (node (ref "PC3") (pin "P") (pinfunction "P_P") (pintype "passive"))
      (node (ref "PC4") (pin "2") (pinfunction "2_2") (pintype "passive"))
      (node (ref "PC5") (pin "N") (pinfunction "N_N") (pintype "passive"))
      (node (ref "PC6") (pin "N") (pinfunction "N_N") (pintype "passive"))
      (node (ref "PC7") (pin "2") (pinfunction "2_2") (pintype "passive"))
      (node (ref "PC8") (pin "2") (pinfunction "2_2") (pintype "passive"))
      (node (ref "PIN") (pin "1") (pinfunction "1_1") (pintype "passive"))
      (node (ref "R2") (pin "2") (pinfunction "2_2") (pintype "passive"))
      (node (ref "R5") (pin "2") (pinfunction "2_2") (pintype "passive"))
      (node (ref "R6") (pin "2") (pinfunction "2_2") (pintype "passive"))
      (node (ref "R9") (pin "2") (pinfunction "2_2") (pintype "passive"))
      (node (ref "RA1") (pin "2") (pinfunction "2_2") (pintype "passive"))
      (node (ref "TD1") (pin "2") (pinfunction "2_2") (pintype "passive"))
      (node (ref "TD2") (pin "2") (pinfunction "2_2") (pintype "passive"))
      (node (ref "TD4") (pin "2") (pinfunction "2_2") (pintype "passive"))
      (node (ref "TD5") (pin "2") (pinfunction "2_2") (pintype "passive"))
    )
    (net (code "35") (name "Net-(IA-+RG)") (class "Default")
      (node (ref "IA") (pin "8") (pinfunction "+RG_8") (pintype "passive"))
      (node (ref "IAG100J") (pin "2") (pintype "bidirectional"))
      (node (ref "IAG10J") (pin "2") (pintype "bidirectional"))
      (node (ref "IAG20J") (pin "2") (pintype "bidirectional"))
      (node (ref "IAG50J") (pin "2") (pintype "bidirectional"))
    )
    (net (code "36") (name "Net-(IA--RG)") (class "Default")
      (node (ref "IA") (pin "1") (pinfunction "-RG_1") (pintype "passive"))
      (node (ref "IAG10") (pin "1") (pinfunction "1_1") (pintype "passive"))
      (node (ref "IAG100") (pin "1") (pinfunction "1_1") (pintype "passive"))
      (node (ref "IAG20") (pin "1") (pinfunction "1_1") (pintype "passive"))
      (node (ref "IAG50") (pin "1") (pinfunction "1_1") (pintype "passive"))
    )
    (net (code "37") (name "Net-(IAG10-Pad2)") (class "Default")
      (node (ref "IAG10") (pin "2") (pinfunction "2_2") (pintype "passive"))
      (node (ref "IAG10J") (pin "1") (pintype "bidirectional"))
    )
    (net (code "38") (name "Net-(IAG20-Pad2)") (class "Default")
      (node (ref "IAG20") (pin "2") (pinfunction "2_2") (pintype "passive"))
      (node (ref "IAG20J") (pin "1") (pintype "bidirectional"))
    )
    (net (code "39") (name "Net-(IAG50-Pad2)") (class "Default")
      (node (ref "IAG50") (pin "2") (pinfunction "2_2") (pintype "passive"))
      (node (ref "IAG50J") (pin "1") (pintype "bidirectional"))
    )
    (net (code "40") (name "Net-(IAG100-Pad2)") (class "Default")
      (node (ref "IAG100") (pin "2") (pinfunction "2_2") (pintype "passive"))
      (node (ref "IAG100J") (pin "1") (pintype "bidirectional"))
    )
    (net (code "41") (name "POS3V3") (class "Default")
      (node (ref "3V3T1") (pin "1") (pintype "input"))
      (node (ref "3V3T2") (pin "1") (pintype "input"))
      (node (ref "3V3T3") (pin "1") (pintype "input"))
      (node (ref "DC2") (pin "1") (pinfunction "1_1") (pintype "passive"))
      (node (ref "DC4") (pin "1") (pinfunction "1_1") (pintype "passive"))
      (node (ref "IA") (pin "7") (pinfunction "+VS_7") (pintype "power_in"))
      (node (ref "IADC3") (pin "1") (pinfunction "1_1") (pintype "passive"))
      (node (ref "IADC4") (pin "P") (pinfunction "P_P") (pintype "passive"))
      (node (ref "LR3") (pin "2") (pinfunction "2_2") (pintype "passive"))
      (node (ref "O") (pin "8") (pinfunction "V+_8") (pintype "power_in"))
      (node (ref "O1") (pin "8") (pinfunction "V+_8") (pintype "power_in"))
      (node (ref "P2") (pin "2") (pinfunction "OUTPUT_2") (pintype "output"))
      (node (ref "PC6") (pin "P") (pinfunction "P_P") (pintype "passive"))
      (node (ref "R8") (pin "1") (pinfunction "1_1") (pintype "passive"))
    )
    (net (code "42") (name "unconnected-(G40-Pad1)") (class "Default")
      (node (ref "G40") (pin "1") (pinfunction "1_1") (pintype "passive"))
    )
    (net (code "43") (name "unconnected-(G40J-Pad2)") (class "Default")
      (node (ref "G40J") (pin "2") (pintype "bidirectional"))
    )
    (net (code "44") (name "unconnected-(GXX-Pad1)") (class "Default")
      (node (ref "GXX") (pin "1") (pinfunction "1_1") (pintype "passive"))
    )
    (net (code "45") (name "unconnected-(GXXJ-Pad2)") (class "Default")
      (node (ref "GXXJ") (pin "2") (pintype "bidirectional"))
    )
    (net (code "46") (name "unconnected-(O-OUTB-Pad7)") (class "Default")
      (node (ref "O") (pin "7") (pinfunction "OUTB_7") (pintype "output"))
    )
  )
)
